# Fleet-Monitor-Accelerometer.net
KiCad netlist of a schematic drawn in Altium Designer
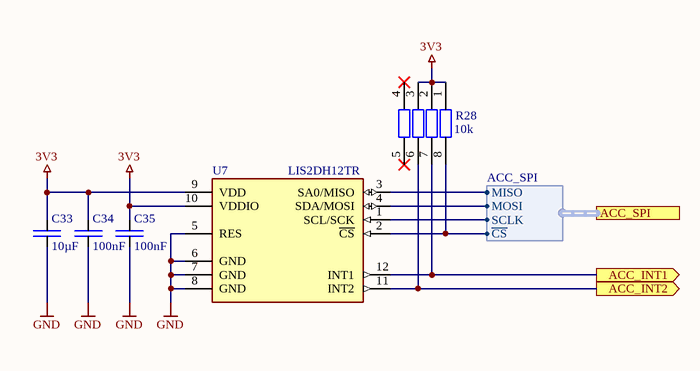
[diagram p0: Fleet-Monitor-Accelerometer.SchDoc]

(export (version "E")
  (design (tool "Eeschema 10.0.6"))
  (components
    (comp (ref "C33")
      (value "10µF")
      (footprint "SMD Keramikkondensator 0603")
      (description "SMD Ceramic Capacitor E6")
      (libsource (lib "Ceramic Capacitors-E6") (part "E6 - 10uF"))
    )
    (comp (ref "C34")
      (value "100nF")
      (footprint "SMD Keramikkondensator 0603")
      (description "SMD Ceramic Capacitor E6")
      (libsource (lib "Ceramic Capacitors-E6") (part "E6 - 100nF"))
    )
    (comp (ref "C35")
      (value "100nF")
      (footprint "SMD Keramikkondensator 0603")
      (description "SMD Ceramic Capacitor E6")
      (libsource (lib "Ceramic Capacitors-E6") (part "E6 - 100nF"))
    )
    (comp (ref "R28")
      (value "10k")
      (footprint "SMD Widerstand Array 4-Fach 0603")
      (description "Isolated Resistor Array")
      (libsource (lib "Fleet-Monitor") (part "R-Array Single Quad E24 - 10k"))
    )
    (comp (ref "U7")
      (value "LIS2DH12TR")
      (footprint "SMD IC LGA-12")
      (description "Accelerometer X, Y, Z Axis ±2g, 4g, 8g, 16g 0.5Hz ~ 672Hz 12-LGA (2x2)")
      (libsource (lib "Fleet-Monitor") (part "LIS2DH12TR"))
    )
  )
  (nets
    (net (code "2") (name "/ACC_INT1") (class "Default")
      (node (ref "R28") (pin "7") (pinfunction "7_7") (pintype "passive"))
      (node (ref "U7") (pin "12") (pinfunction "INT1_12") (pintype "output"))
    )
    (net (code "3") (name "/ACC_INT2") (class "Default")
      (node (ref "R28") (pin "6") (pinfunction "6_6") (pintype "passive"))
      (node (ref "U7") (pin "11") (pinfunction "INT2_11") (pintype "output"))
    )
    (net (code "4") (name "/MISO") (class "Default")
      (node (ref "U7") (pin "3") (pinfunction "SA0/MISO_3") (pintype "bidirectional"))
    )
    (net (code "5") (name "/MOSI") (class "Default")
      (node (ref "U7") (pin "4") (pinfunction "SDA/MOSI_4") (pintype "bidirectional"))
    )
    (net (code "6") (name "/SCLK") (class "Default")
      (node (ref "U7") (pin "1") (pinfunction "SCL/SCK_1") (pintype "input"))
    )
    (net (code "8") (name "/~{CS}") (class "Default")
      (node (ref "R28") (pin "8") (pinfunction "8_8") (pintype "passive"))
      (node (ref "U7") (pin "2") (pinfunction "~{CS}_2") (pintype "input"))
    )
    (net (code "9") (name "3V3") (class "Default")
      (node (ref "C33") (pin "2") (pinfunction "2_2") (pintype "passive"))
      (node (ref "C34") (pin "2") (pinfunction "2_2") (pintype "passive"))
      (node (ref "C35") (pin "2") (pinfunction "2_2") (pintype "passive"))
      (node (ref "R28") (pin "1") (pinfunction "1_1") (pintype "passive"))
      (node (ref "R28") (pin "2") (pinfunction "2_2") (pintype "passive"))
      (node (ref "R28") (pin "3") (pinfunction "3_3") (pintype "passive"))
      (node (ref "U7") (pin "10") (pinfunction "VDDIO_10") (pintype "passive"))
      (node (ref "U7") (pin "9") (pinfunction "VDD_9") (pintype "passive"))
    )
    (net (code "10") (name "GND") (class "Default")
      (node (ref "C33") (pin "1") (pinfunction "1_1") (pintype "passive"))
      (node (ref "C34") (pin "1") (pinfunction "1_1") (pintype "passive"))
      (node (ref "C35") (pin "1") (pinfunction "1_1") (pintype "passive"))
      (node (ref "U7") (pin "5") (pinfunction "RES_5") (pintype "passive"))
      (node (ref "U7") (pin "6") (pinfunction "GND_6") (pintype "passive"))
      (node (ref "U7") (pin "7") (pinfunction "GND_7") (pintype "passive"))
      (node (ref "U7") (pin "8") (pinfunction "GND_8") (pintype "passive"))
    )
    (net (code "11") (name "unconnected-(R28-Pad4)") (class "Default")
      (node (ref "R28") (pin "4") (pinfunction "4_4") (pintype "passive+no_connect"))
    )
    (net (code "12") (name "unconnected-(R28-Pad5)") (class "Default")
      (node (ref "R28") (pin "5") (pinfunction "5_5") (pintype "passive+no_connect"))
    )
  )
)
